# Vex-Field-Controller-SCH_2025-05-28.net
KiCad netlist of a schematic drawn in Altium Designer
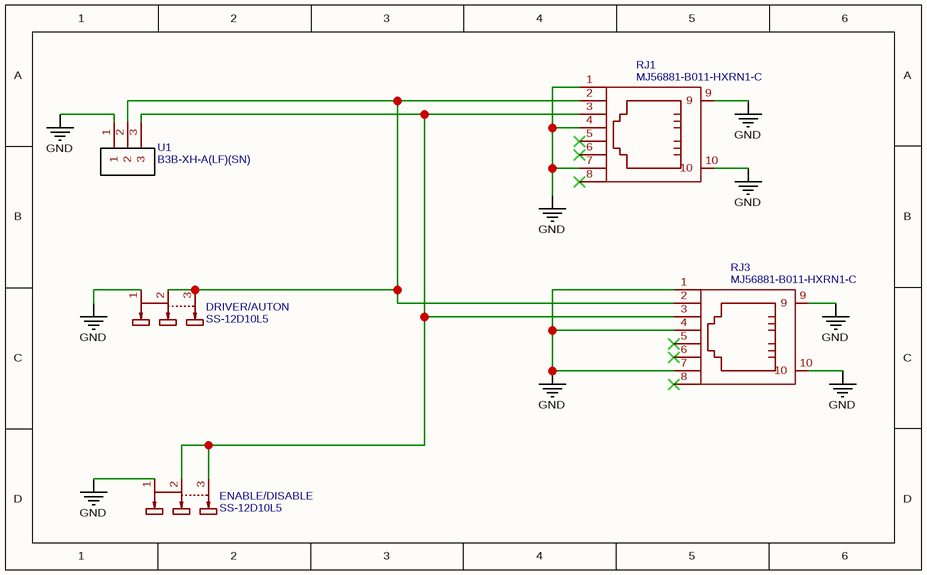
[diagram p0: Vex-Field-Controller-SCH_2025-05-28.schdoc]

(export (version "E")
  (design (tool "Eeschema 10.0.6"))
  (components
    (comp (ref "DRIVER/AUTON")
      (value "SS-12D10L5")
      (fields (field (name "MANUFACTURER") "XKB Connectivity(中国星坤)") (field (name "CONTRIBUTOR") "LCSC"))
      (libsource (lib "altium-import") (part "root_0_SS-12D10L5_"))
    )
    (comp (ref "ENABLE/DISABLE")
      (value "SS-12D10L5")
      (fields (field (name "MANUFACTURER") "XKB Connectivity(中国星坤)") (field (name "CONTRIBUTOR") "LCSC"))
      (libsource (lib "altium-import") (part "root_0_SS-12D10L5_"))
    )
    (comp (ref "RJ1")
      (value "MJ56881-B011-HXRN1-C")
      (fields
        (field (name "MANUFACTURER") "Heling(合陵)")
        (field (name "MANUFACTURER PART") "MJ56881-B011-HLRN1-C")
        (field (name "CONTRIBUTOR") "LCSC")
      )
      (libsource (lib "altium-import") (part "root_3_MJ56881-B011-HXRN1-C_"))
    )
    (comp (ref "RJ3")
      (value "MJ56881-B011-HXRN1-C")
      (fields
        (field (name "MANUFACTURER") "Heling(合陵)")
        (field (name "MANUFACTURER PART") "MJ56881-B011-HLRN1-C")
        (field (name "CONTRIBUTOR") "LCSC")
      )
      (libsource (lib "altium-import") (part "root_3_MJ56881-B011-HXRN1-C_"))
    )
    (comp (ref "U1")
      (value "B3B-XH-A(LF)(SN)")
      (fields (field (name "MANUFACTURER") "JST") (field (name "CONTRIBUTOR") "LCSC"))
      (libsource (lib "altium-import") (part "root_0_B3B-XH-A(LF)(SN)_"))
    )
  )
  (nets
    (net (code "1") (name "GND") (class "Default")
      (node (ref "DRIVER/AUTON") (pin "1") (pinfunction "1_1") (pintype "passive"))
      (node (ref "ENABLE/DISABLE") (pin "1") (pinfunction "1_1") (pintype "passive"))
      (node (ref "RJ1") (pin "1") (pinfunction "1_1") (pintype "passive"))
      (node (ref "RJ1") (pin "10") (pinfunction "10_10") (pintype "passive"))
      (node (ref "RJ1") (pin "4") (pinfunction "4_4") (pintype "passive"))
      (node (ref "RJ1") (pin "7") (pinfunction "7_7") (pintype "passive"))
      (node (ref "RJ1") (pin "9") (pinfunction "9_9") (pintype "passive"))
      (node (ref "RJ3") (pin "1") (pinfunction "1_1") (pintype "passive"))
      (node (ref "RJ3") (pin "10") (pinfunction "10_10") (pintype "passive"))
      (node (ref "RJ3") (pin "4") (pinfunction "4_4") (pintype "passive"))
      (node (ref "RJ3") (pin "7") (pinfunction "7_7") (pintype "passive"))
      (node (ref "RJ3") (pin "9") (pinfunction "9_9") (pintype "passive"))
      (node (ref "U1") (pin "1") (pinfunction "1_1") (pintype "passive"))
    )
    (net (code "2") (name "Net-(DRIVER/AUTON-Pad2)") (class "Default")
      (node (ref "DRIVER/AUTON") (pin "2") (pinfunction "2_2") (pintype "passive"))
      (node (ref "DRIVER/AUTON") (pin "3") (pinfunction "3_3") (pintype "passive"))
      (node (ref "RJ1") (pin "2") (pinfunction "2_2") (pintype "passive"))
      (node (ref "RJ3") (pin "2") (pinfunction "2_2") (pintype "passive"))
      (node (ref "U1") (pin "2") (pinfunction "2_2") (pintype "passive"))
    )
    (net (code "3") (name "Net-(ENABLE/DISABLE-Pad2)") (class "Default")
      (node (ref "ENABLE/DISABLE") (pin "2") (pinfunction "2_2") (pintype "passive"))
      (node (ref "ENABLE/DISABLE") (pin "3") (pinfunction "3_3") (pintype "passive"))
      (node (ref "RJ1") (pin "3") (pinfunction "3_3") (pintype "passive"))
      (node (ref "RJ3") (pin "3") (pinfunction "3_3") (pintype "passive"))
      (node (ref "U1") (pin "3") (pinfunction "3_3") (pintype "passive"))
    )
    (net (code "4") (name "unconnected-(RJ1-Pad5)") (class "Default")
      (node (ref "RJ1") (pin "5") (pinfunction "5_5") (pintype "passive+no_connect"))
    )
    (net (code "5") (name "unconnected-(RJ1-Pad6)") (class "Default")
      (node (ref "RJ1") (pin "6") (pinfunction "6_6") (pintype "passive+no_connect"))
    )
    (net (code "6") (name "unconnected-(RJ1-Pad8)") (class "Default")
      (node (ref "RJ1") (pin "8") (pinfunction "8_8") (pintype "passive+no_connect"))
    )
    (net (code "7") (name "unconnected-(RJ3-Pad5)") (class "Default")
      (node (ref "RJ3") (pin "5") (pinfunction "5_5") (pintype "passive+no_connect"))
    )
    (net (code "8") (name "unconnected-(RJ3-Pad6)") (class "Default")
      (node (ref "RJ3") (pin "6") (pinfunction "6_6") (pintype "passive+no_connect"))
    )
    (net (code "9") (name "unconnected-(RJ3-Pad8)") (class "Default")
      (node (ref "RJ3") (pin "8") (pinfunction "8_8") (pintype "passive+no_connect"))
    )
  )
)
